# tracker_usb_c.net
KiCad netlist of a schematic drawn in Altium Designer
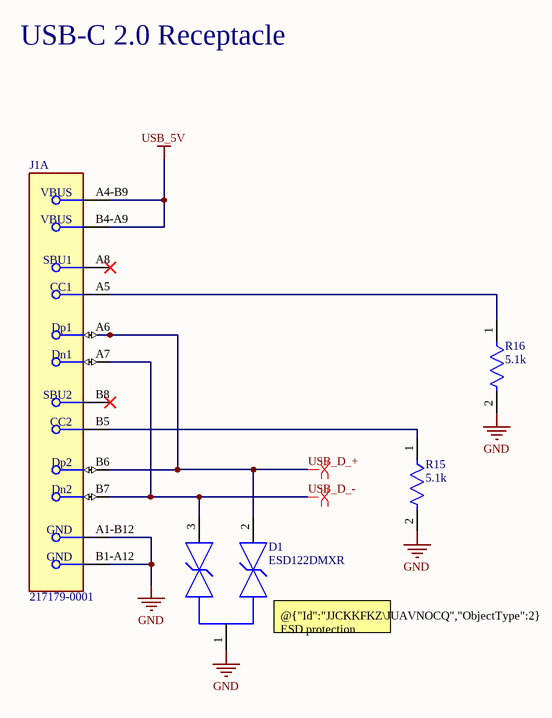
[diagram p0: tracker_usb_c.SchDoc]

(export (version "E")
  (design (tool "Eeschema 10.0.6"))
  (components
    (comp (ref "D1")
      (value "ESD122DMXR")
      (footprint "FP-DMX0003A-MFG")
      (description "TVS DIODE 3.6V 8.4V 3X2SON")
      (libsource (lib "Altium Content Vault") (part "7ac44b7b55cb7aaaff233ca2b760964"))
    )
    (comp (ref "J1")
      (value "217179-0001")
      (footprint "FP-2171790001-MFG")
      (description "CONN RCP USB2.0 TYP C 24P SMD RA")
      (libsource (lib "Altium Content Vault") (part "8b86497a633d14b3f74642136fc0ce6"))
    )
    (comp (ref "R15")
      (value "5.1k")
      (footprint "FP-MCT0603-IPC_B")
      (description "RES SMD 100 OHM 1% 1/8W 0603")
      (fields (field (name "TOLERANCE") "0.1%"))
      (libsource (lib "Altium Content Vault") (part "1029c3af85768c4190bb7ad29bc67b5"))
    )
    (comp (ref "R16")
      (value "5.1k")
      (footprint "FP-MCT0603-IPC_B")
      (description "RES SMD 100 OHM 1% 1/8W 0603")
      (fields (field (name "TOLERANCE") "0.1%"))
      (libsource (lib "Altium Content Vault") (part "1029c3af85768c4190bb7ad29bc67b5"))
    )
  )
  (nets
    (net (code "1") (name "/USB_D_+") (class "Default")
      (node (ref "D1") (pin "2") (pinfunction "IO1_2") (pintype "passive"))
      (node (ref "J1") (pin "A6") (pinfunction "Dp1_A6") (pintype "bidirectional"))
      (node (ref "J1") (pin "B6") (pinfunction "Dp2_B6") (pintype "bidirectional"))
    )
    (net (code "2") (name "/USB_D_-") (class "Default")
      (node (ref "D1") (pin "3") (pinfunction "IO2_3") (pintype "passive"))
      (node (ref "J1") (pin "A7") (pinfunction "Dn1_A7") (pintype "bidirectional"))
      (node (ref "J1") (pin "B7") (pinfunction "Dn2_B7") (pintype "bidirectional"))
    )
    (net (code "3") (name "GND") (class "Default")
      (node (ref "D1") (pin "1") (pinfunction "GND_1") (pintype "power_in"))
      (node (ref "J1") (pin "A1-B12") (pinfunction "GND_A1-B12") (pintype "power_in"))
      (node (ref "J1") (pin "B1-A12") (pinfunction "GND_B1-A12") (pintype "power_in"))
      (node (ref "R15") (pin "2") (pinfunction "2_2") (pintype "passive"))
      (node (ref "R16") (pin "2") (pinfunction "2_2") (pintype "passive"))
    )
    (net (code "4") (name "Net-(J1A-CC1)") (class "Default")
      (node (ref "J1") (pin "A5") (pinfunction "CC1_A5") (pintype "passive"))
      (node (ref "R16") (pin "1") (pinfunction "1_1") (pintype "passive"))
    )
    (net (code "5") (name "Net-(J1A-CC2)") (class "Default")
      (node (ref "J1") (pin "B5") (pinfunction "CC2_B5") (pintype "passive"))
      (node (ref "R15") (pin "1") (pinfunction "1_1") (pintype "passive"))
    )
    (net (code "6") (name "USB_5V") (class "Default")
      (node (ref "J1") (pin "A4-B9") (pinfunction "VBUS_A4-B9") (pintype "power_in"))
      (node (ref "J1") (pin "B4-A9") (pinfunction "VBUS_B4-A9") (pintype "power_in"))
    )
    (net (code "7") (name "unconnected-(J1A-SBU1-PadA8)") (class "Default")
      (node (ref "J1") (pin "A8") (pinfunction "SBU1_A8") (pintype "passive+no_connect"))
    )
    (net (code "8") (name "unconnected-(J1A-SBU2-PadB8)") (class "Default")
      (node (ref "J1") (pin "B8") (pinfunction "SBU2_B8") (pintype "passive+no_connect"))
    )
  )
)
